# V2_0.net
KiCad netlist of a schematic drawn in Altium Designer
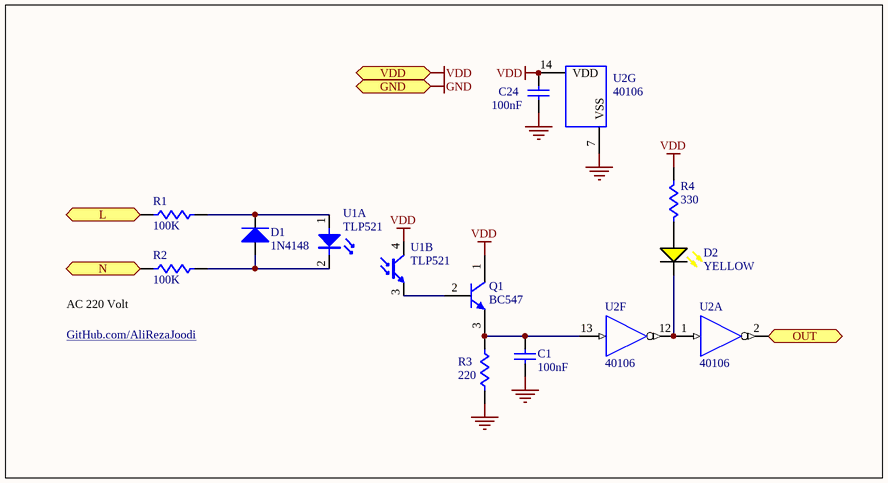
[diagram p0: V2.0.SchDoc]

(export (version "E")
  (design (tool "Eeschema 10.0.6"))
  (components
    (comp (ref "C1")
      (value "100nF")
      (footprint "CAPNTO5.08-7.37x3.94")
      (description "Capacitor")
      (fields (field (name "MANUFACTURER") "Generic Components") (field (name "PUBLISHER") "Altium Limited"))
      (libsource (lib "Miscellaneous Devices") (part "Cap"))
    )
    (comp (ref "C24")
      (value "100nF")
      (footprint "0805")
      (description "Capacitor")
      (fields (field (name "PUBLISHER") "Altium Limited"))
      (libsource (lib "Miscellaneous Devices") (part "Cap"))
    )
    (comp (ref "D1")
      (value "1N4148")
      (footprint "DIODE0.2_")
      (description "Default Diode")
      (fields (field (name "MANUFACTURER") "Generic Components") (field (name "PUBLISHER") "Altium Limited"))
      (libsource (lib "Miscellaneous Devices") (part "Diode"))
    )
    (comp (ref "D2")
      (value "YELLOW")
      (footprint "LED_THD_5MM_YELLOW")
      (description "LED, Yellow")
      (fields (field (name "MANUFACTURER") "Generic Components") (field (name "PUBLISHER") "Altium Limited"))
      (libsource (lib "Display") (part "LED_YELLOW"))
    )
    (comp (ref "Q1")
      (value "BC547")
      (footprint "TO92C")
      (description "Silicon Bipolar Transistor")
      (libsource (lib "my Libraries") (part "NPN"))
    )
    (comp (ref "R1")
      (value "100K")
      (footprint "AXIAL-0.4")
      (description "Resistor")
      (fields (field (name "MANUFACTURER") "Generic Components") (field (name "PUBLISHER") "Altium Limited"))
      (libsource (lib "Miscellaneous Devices") (part "Res1"))
    )
    (comp (ref "R2")
      (value "100K")
      (footprint "AXIAL-0.4")
      (description "Resistor")
      (fields (field (name "MANUFACTURER") "Generic Components") (field (name "PUBLISHER") "Altium Limited"))
      (libsource (lib "Miscellaneous Devices") (part "Res1"))
    )
    (comp (ref "R3")
      (value "220")
      (footprint "AXIAL-0.4")
      (description "Resistor")
      (fields (field (name "MANUFACTURER") "Generic Components") (field (name "PUBLISHER") "Altium Limited"))
      (libsource (lib "Miscellaneous Devices") (part "Res1"))
    )
    (comp (ref "R4")
      (value "330")
      (footprint "0805")
      (description "Resistor")
      (fields (field (name "MANUFACTURER") "Generic Components") (field (name "PUBLISHER") "Altium Limited"))
      (libsource (lib "Miscellaneous Devices") (part "Res1"))
    )
    (comp (ref "U1")
      (value "TLP521")
      (footprint "DIP-4")
      (fields (field (name "PUBLISHER") "Altium Limited"))
      (libsource (lib "my Libraries") (part "Optoisolator"))
    )
    (comp (ref "U2")
      (value "40106")
      (footprint "DIP14")
      (description "Hex inverting Schmitt trigger, 14-Pin")
      (fields (field (name "PUBLISHER") "Altium Limited"))
      (libsource (lib "my Libraries") (part "40106"))
    )
  )
  (nets
    (net (code "1") (name "/L") (class "Default")
      (node (ref "R1") (pin "1") (pinfunction "1_1") (pintype "passive"))
    )
    (net (code "2") (name "/N") (class "Default")
      (node (ref "R2") (pin "1") (pinfunction "1_1") (pintype "passive"))
    )
    (net (code "3") (name "/OUT") (class "Default")
      (node (ref "U2") (pin "2") (pinfunction "~{O}_2") (pintype "output"))
    )
    (net (code "4") (name "GND") (class "Default")
      (node (ref "C1") (pin "1") (pinfunction "1_1") (pintype "passive"))
      (node (ref "C24") (pin "2") (pinfunction "2_2") (pintype "passive"))
      (node (ref "R3") (pin "2") (pinfunction "2_2") (pintype "passive"))
      (node (ref "U2") (pin "7") (pinfunction "VSS_7") (pintype "power_in"))
    )
    (net (code "5") (name "Net-(D1-A)") (class "Default")
      (node (ref "D1") (pin "1") (pinfunction "A_1") (pintype "passive"))
      (node (ref "R2") (pin "2") (pinfunction "2_2") (pintype "passive"))
      (node (ref "U1") (pin "2") (pinfunction "K_2") (pintype "power_in"))
    )
    (net (code "6") (name "Net-(D1-K)") (class "Default")
      (node (ref "D1") (pin "2") (pinfunction "K_2") (pintype "passive"))
      (node (ref "R1") (pin "2") (pinfunction "2_2") (pintype "passive"))
      (node (ref "U1") (pin "1") (pinfunction "A_1") (pintype "power_in"))
    )
    (net (code "7") (name "Net-(D2-A)") (class "Default")
      (node (ref "D2") (pin "1") (pinfunction "A_1") (pintype "passive"))
      (node (ref "R4") (pin "1") (pinfunction "1_1") (pintype "passive"))
    )
    (net (code "8") (name "Net-(D2-K)") (class "Default")
      (node (ref "D2") (pin "2") (pinfunction "K_2") (pintype "passive"))
      (node (ref "U2") (pin "1") (pinfunction "I_1") (pintype "input"))
      (node (ref "U2") (pin "12") (pinfunction "~{O}_12") (pintype "output"))
    )
    (net (code "9") (name "Net-(Q1-B)") (class "Default")
      (node (ref "Q1") (pin "2") (pinfunction "B_2") (pintype "passive"))
      (node (ref "U1") (pin "3") (pinfunction "E_3") (pintype "passive"))
    )
    (net (code "10") (name "Net-(Q1-E)") (class "Default")
      (node (ref "C1") (pin "2") (pinfunction "2_2") (pintype "passive"))
      (node (ref "Q1") (pin "3") (pinfunction "E_3") (pintype "passive"))
      (node (ref "R3") (pin "1") (pinfunction "1_1") (pintype "passive"))
      (node (ref "U2") (pin "13") (pinfunction "I_13") (pintype "input"))
    )
    (net (code "11") (name "VDD") (class "Default")
      (node (ref "C24") (pin "1") (pinfunction "1_1") (pintype "passive"))
      (node (ref "Q1") (pin "1") (pinfunction "C_1") (pintype "passive"))
      (node (ref "R4") (pin "2") (pinfunction "2_2") (pintype "passive"))
      (node (ref "U1") (pin "4") (pinfunction "C_4") (pintype "passive"))
      (node (ref "U2") (pin "14") (pinfunction "VDD_14") (pintype "passive"))
    )
  )
)
